# PROC051C_XDS110_Interface_1B.net
KiCad netlist of a schematic drawn in Altium Designer
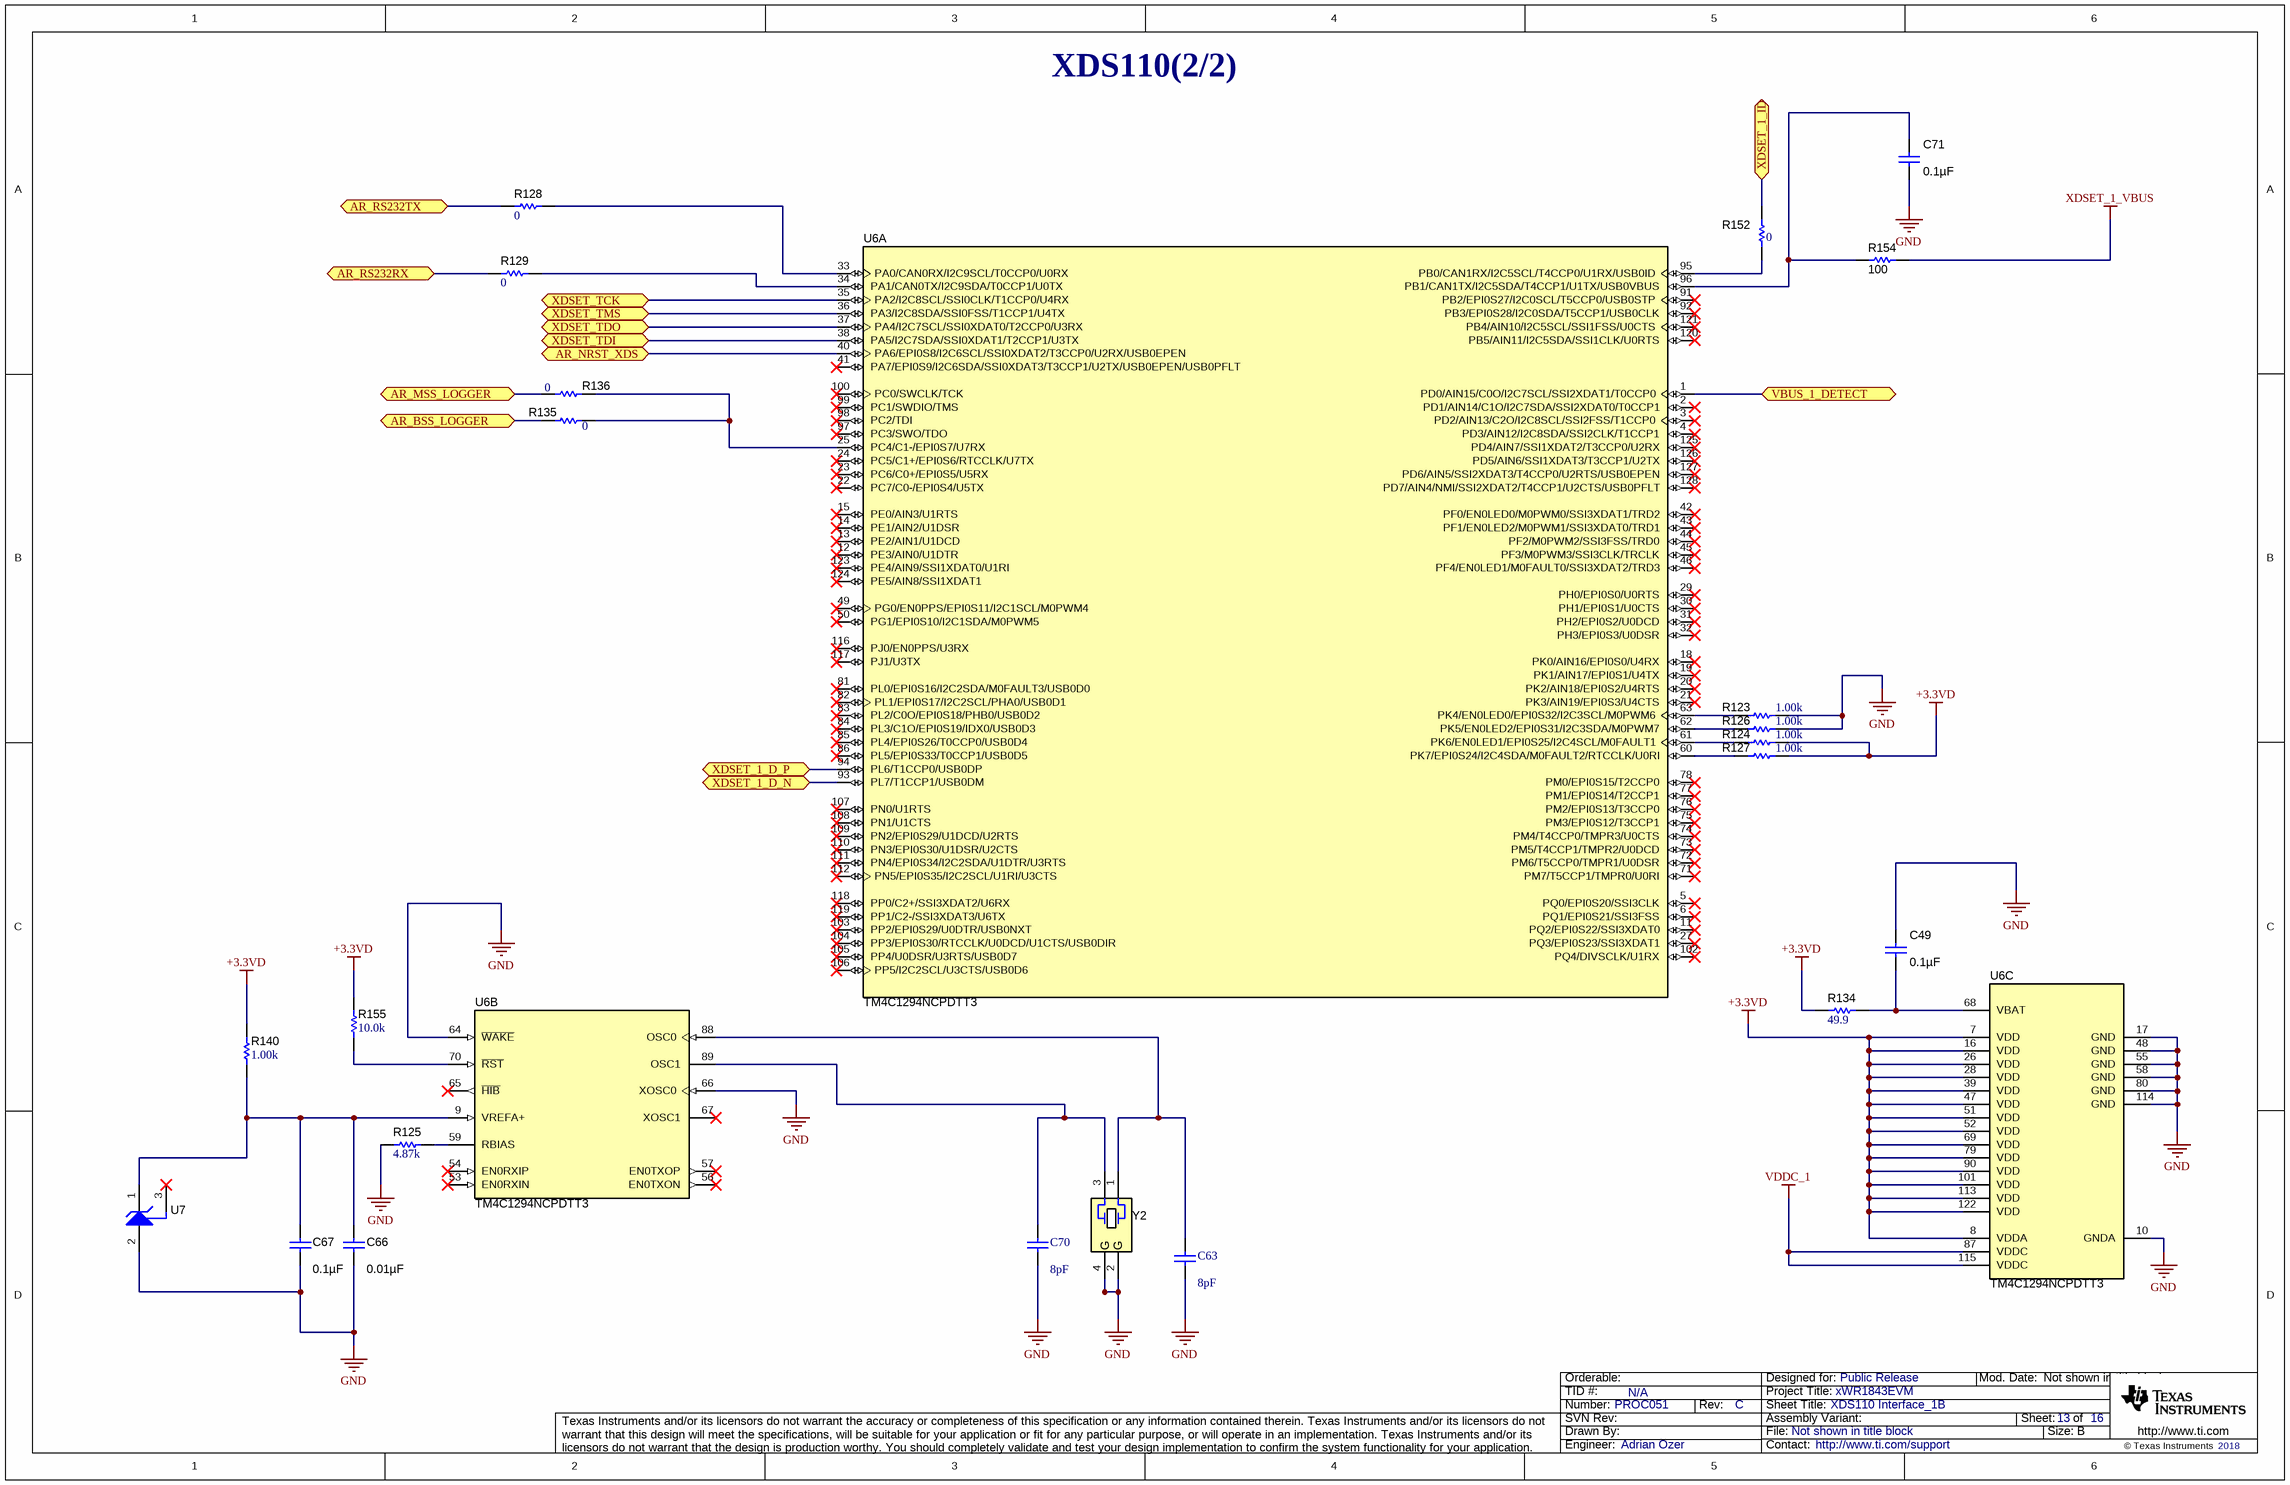
[diagram p0: PROC051C_XDS110 Interface_1B.SchDoc]

(export (version "E")
  (design (tool "Eeschema 10.0.6"))
  (components
    (comp (ref "C49")
      (value "C0402C104K8RACTU")
      (footprint "0402L")
      (description "CAP, CERM, 0.1 µF, 10 V,+/- 10%, X7R, 0402")
      (fields (field (name "MANUFACTURER") "Kemet") (field (name "VALUEDISPLAYED") "0.1µF"))
      (libsource (lib "Altium Vault - TI") (part "CMP-0078241-1"))
    )
    (comp (ref "C63")
      (value "GCM1555C1H8R0DA16D")
      (footprint "0402L")
      (description "Cap Ceramic 8pF 50V C0G 0.5pF SMD 0402 125C Paper T/R")
      (fields (field (name "CAP_F") "8pF") (field (name "MANUFACTURER") "Murata Electronics North America"))
      (libsource (lib "Altium Vault - TI") (part "CMP-0087060-3"))
    )
    (comp (ref "C66")
      (value "C0402C103K4RACTU")
      (footprint "0402L")
      (description "CAP, CERM, 0.01 µF, 16 V,+/- 10%, X7R, 0402")
      (fields (field (name "MANUFACTURER") "Kemet") (field (name "VALUEDISPLAYED") "0.01µF"))
      (libsource (lib "Altium Vault - TI") (part "Capacitor"))
    )
    (comp (ref "C67")
      (value "C0402C104K8RACTU")
      (footprint "0402L")
      (description "CAP, CERM, 0.1 µF, 10 V,+/- 10%, X7R, 0402")
      (fields (field (name "MANUFACTURER") "Kemet") (field (name "VALUEDISPLAYED") "0.1µF"))
      (libsource (lib "Altium Vault - TI") (part "Capacitor"))
    )
    (comp (ref "C70")
      (value "GCM1555C1H8R0DA16D")
      (footprint "0402L")
      (description "Cap Ceramic 8pF 50V C0G 0.5pF SMD 0402 125C Paper T/R")
      (fields (field (name "CAP_F") "8pF") (field (name "MANUFACTURER") "Murata Electronics North America"))
      (libsource (lib "Altium Vault - TI") (part "CMP-0087060-3"))
    )
    (comp (ref "C71")
      (value "C0402C104K8RACTU")
      (footprint "0402L")
      (description "CAP, CERM, 0.1 µF, 10 V,+/- 10%, X7R, 0402")
      (fields (field (name "MANUFACTURER") "Kemet") (field (name "VALUEDISPLAYED") "0.1µF"))
      (libsource (lib "Altium Vault - TI") (part "Capacitor"))
    )
    (comp (ref "R123")
      (value "CRCW04021K00FKED")
      (footprint "0402L")
      (description "RES, 1.00 k, 1%, 0.063 W, AEC-Q200 Grade 0, 0402")
      (fields (field (name "MANUFACTURER") "Vishay-Dale") (field (name "VALUEDISPLAYED") "1.00k"))
      (libsource (lib "Altium Vault - TI") (part "Resistor"))
    )
    (comp (ref "R124")
      (value "CRCW04021K00FKED")
      (footprint "0402L")
      (description "RES, 1.00 k, 1%, 0.063 W, AEC-Q200 Grade 0, 0402")
      (fields (field (name "MANUFACTURER") "Vishay-Dale") (field (name "VALUEDISPLAYED") "1.00k"))
      (libsource (lib "Altium Vault - TI") (part "Resistor"))
    )
    (comp (ref "R125")
      (value "CRCW04024K87FKED")
      (footprint "0402L")
      (description "RES, 4.87 k, 1%, 0.063 W, AEC-Q200 Grade 0, 0402")
      (fields (field (name "MANUFACTURER") "Vishay-Dale") (field (name "VALUEDISPLAYED") "4.87k"))
      (libsource (lib "Altium Vault - TI") (part "Resistor"))
    )
    (comp (ref "R126")
      (value "CRCW04021K00FKED")
      (footprint "0402L")
      (description "RES, 1.00 k, 1%, 0.063 W, AEC-Q200 Grade 0, 0402")
      (fields (field (name "MANUFACTURER") "Vishay-Dale") (field (name "VALUEDISPLAYED") "1.00k"))
      (libsource (lib "Altium Vault - TI") (part "Resistor"))
    )
    (comp (ref "R127")
      (value "CRCW04021K00FKED")
      (footprint "0402L")
      (description "RES, 1.00 k, 1%, 0.063 W, AEC-Q200 Grade 0, 0402")
      (fields (field (name "MANUFACTURER") "Vishay-Dale") (field (name "VALUEDISPLAYED") "1.00k"))
      (libsource (lib "Altium Vault - TI") (part "Resistor"))
    )
    (comp (ref "R128")
      (value "ERJ-2GE0R00X")
      (footprint "0402L")
      (description "RES, 0, 5%, 0.1 W, AEC-Q200 Grade 0, 0402")
      (fields (field (name "MANUFACTURER") "Panasonic") (field (name "VALUEDISPLAYED") "0"))
      (libsource (lib "Altium Vault - TI") (part "Resistor"))
    )
    (comp (ref "R129")
      (value "ERJ-2GE0R00X")
      (footprint "0402L")
      (description "RES, 0, 5%, 0.1 W, AEC-Q200 Grade 0, 0402")
      (fields (field (name "MANUFACTURER") "Panasonic") (field (name "VALUEDISPLAYED") "0"))
      (libsource (lib "Altium Vault - TI") (part "Resistor"))
    )
    (comp (ref "R134")
      (value "CRCW040249R9FKED")
      (footprint "0402L")
      (description "RES, 49.9, 1%, 0.063 W, AEC-Q200 Grade 0, 0402")
      (fields (field (name "MANUFACTURER") "Vishay-Dale") (field (name "VALUEDISPLAYED") "49.9"))
      (libsource (lib "Altium Vault - TI") (part "Resistor"))
    )
    (comp (ref "R135")
      (value "CRCW02010000Z0ED")
      (footprint "0201_Silk")
      (description "RES, 0, 5%, 0.05 W, 0201")
      (fields (field (name "MANUFACTURER") "Vishay-Dale") (field (name "VALUEDISPLAYED") "0"))
      (libsource (lib "Altium Vault - TI") (part "Resistor"))
    )
    (comp (ref "R136")
      (value "CRCW02010000Z0ED")
      (footprint "0201_Silk")
      (description "RES, 0, 5%, 0.05 W, 0201")
      (fields (field (name "MANUFACTURER") "Vishay-Dale") (field (name "VALUEDISPLAYED") "0"))
      (libsource (lib "Altium Vault - TI") (part "Resistor"))
    )
    (comp (ref "R140")
      (value "CRCW04021K00FKED")
      (footprint "0402L")
      (description "RES, 1.00 k, 1%, 0.063 W, AEC-Q200 Grade 0, 0402")
      (fields (field (name "MANUFACTURER") "Vishay-Dale") (field (name "VALUEDISPLAYED") "1.00k"))
      (libsource (lib "Altium Vault - TI") (part "Resistor"))
    )
    (comp (ref "R152")
      (value "ERJ-2GE0R00X")
      (footprint "0402L")
      (description "RES, 0, 5%, 0.1 W, AEC-Q200 Grade 0, 0402")
      (fields (field (name "MANUFACTURER") "Panasonic") (field (name "VALUEDISPLAYED") "0"))
      (libsource (lib "Altium Vault - TI") (part "Resistor"))
    )
    (comp (ref "R154")
      (value "ERJ-2GEJ101X")
      (footprint "0402L")
      (description "RES, 100, 5%, 0.1 W, AEC-Q200 Grade 0, 0402")
      (fields
        (field (name "MANUFACTURER") "Panasonic")
        (field (name "VALUEDISPLAYED") "100")
        (field (name "PUBLISHER") "Texas Instruments")
      )
      (libsource (lib "Altium Vault - TI") (part "Resistor"))
    )
    (comp (ref "R155")
      (value "CRCW040210K0FKED")
      (footprint "0402L")
      (description "RES, 10.0 k, 1%, 0.063 W, AEC-Q200 Grade 0, 0402")
      (fields (field (name "MANUFACTURER") "Vishay-Dale") (field (name "VALUEDISPLAYED") "10.0k"))
      (libsource (lib "Altium Vault - TI") (part "Resistor"))
    )
    (comp (ref "U6")
      (value "TM4C1294NCPDTT3")
      (footprint "PDT0128A")
      (fields (field (name "PARTNUMBER") "TM4C1294NCPDTT3") (field (name "MANUFACTURER") "Texas Instruments"))
      (libsource (lib "Altium Vault - TI") (part "TI-TM4C1294NCPDT-128"))
    )
    (comp (ref "U7")
      (value "LM4040C25QDBZR")
      (footprint "DBZ0003A_N")
      (fields (field (name "MANUFACTURER") "Texas Instruments"))
      (libsource (lib "Altium Vault - TI") (part "TI-LM4040C25DBZ3"))
    )
    (comp (ref "Y2")
      (value "NX3225SA-16.000M-STD-CRS-2")
      (footprint "NDK_NX3225SA")
      (description "Crystal, 16 MHz, 15 ppm, 8 pF, AEC-Q200 Grade 1, SMD")
      (fields (field (name "MANUFACTURER") "NDK"))
      (libsource (lib "Altium Vault - TI") (part "CMP-0078214-2"))
    )
  )
  (nets
    (net (code "1") (name "+3.3VD") (class "Default")
      (node (ref "R124") (pin "2") (pinfunction "2_2") (pintype "passive"))
      (node (ref "R127") (pin "2") (pinfunction "2_2") (pintype "passive"))
      (node (ref "R134") (pin "2") (pinfunction "2_2") (pintype "passive"))
      (node (ref "R140") (pin "2") (pinfunction "2_2") (pintype "passive"))
      (node (ref "R155") (pin "2") (pinfunction "2_2") (pintype "passive"))
      (node (ref "U6") (pin "101") (pinfunction "VDD_101") (pintype "power_in"))
      (node (ref "U6") (pin "113") (pinfunction "VDD_113") (pintype "power_in"))
      (node (ref "U6") (pin "122") (pinfunction "VDD_122") (pintype "power_in"))
      (node (ref "U6") (pin "16") (pinfunction "VDD_16") (pintype "power_in"))
      (node (ref "U6") (pin "26") (pinfunction "VDD_26") (pintype "power_in"))
      (node (ref "U6") (pin "28") (pinfunction "VDD_28") (pintype "power_in"))
      (node (ref "U6") (pin "39") (pinfunction "VDD_39") (pintype "power_in"))
      (node (ref "U6") (pin "47") (pinfunction "VDD_47") (pintype "power_in"))
      (node (ref "U6") (pin "51") (pinfunction "VDD_51") (pintype "power_in"))
      (node (ref "U6") (pin "52") (pinfunction "VDD_52") (pintype "power_in"))
      (node (ref "U6") (pin "69") (pinfunction "VDD_69") (pintype "power_in"))
      (node (ref "U6") (pin "7") (pinfunction "VDD_7") (pintype "power_in"))
      (node (ref "U6") (pin "79") (pinfunction "VDD_79") (pintype "power_in"))
      (node (ref "U6") (pin "8") (pinfunction "VDDA_8") (pintype "power_in"))
      (node (ref "U6") (pin "90") (pinfunction "VDD_90") (pintype "power_in"))
    )
    (net (code "2") (name "/AR_BSS_LOGGER") (class "Default")
      (node (ref "R135") (pin "1") (pinfunction "1_1") (pintype "passive"))
    )
    (net (code "3") (name "/AR_MSS_LOGGER") (class "Default")
      (node (ref "R136") (pin "1") (pinfunction "1_1") (pintype "passive"))
    )
    (net (code "4") (name "/AR_NRST_XDS") (class "Default")
      (node (ref "U6") (pin "40") (pinfunction "PA6/EPI0S8/I2C6SCL/SSI0XDAT2/T3CCP0/U2RX/USB0EPEN_40") (pintype "bidirectional"))
    )
    (net (code "5") (name "/AR_RS232RX") (class "Default")
      (node (ref "R129") (pin "1") (pinfunction "1_1") (pintype "passive"))
    )
    (net (code "6") (name "/AR_RS232TX") (class "Default")
      (node (ref "R128") (pin "1") (pinfunction "1_1") (pintype "passive"))
    )
    (net (code "7") (name "/VBUS_1_DETECT") (class "Default")
      (node (ref "U6") (pin "1") (pinfunction "PD0/AIN15/C0O/I2C7SCL/SSI2XDAT1/T0CCP0_1") (pintype "bidirectional"))
    )
    (net (code "8") (name "/XDSET_1_D_N") (class "Default")
      (node (ref "U6") (pin "93") (pinfunction "PL7/T1CCP1/USB0DM_93") (pintype "bidirectional"))
    )
    (net (code "9") (name "/XDSET_1_D_P") (class "Default")
      (node (ref "U6") (pin "94") (pinfunction "PL6/T1CCP0/USB0DP_94") (pintype "bidirectional"))
    )
    (net (code "10") (name "/XDSET_1_ID") (class "Default")
      (node (ref "R152") (pin "2") (pinfunction "2_2") (pintype "passive"))
    )
    (net (code "11") (name "/XDSET_TCK") (class "Default")
      (node (ref "U6") (pin "35") (pinfunction "PA2/I2C8SCL/SSI0CLK/T1CCP0/U4RX_35") (pintype "bidirectional"))
    )
    (net (code "12") (name "/XDSET_TDI") (class "Default")
      (node (ref "U6") (pin "38") (pinfunction "PA5/I2C7SDA/SSI0XDAT1/T2CCP1/U3TX_38") (pintype "bidirectional"))
    )
    (net (code "13") (name "/XDSET_TDO") (class "Default")
      (node (ref "U6") (pin "37") (pinfunction "PA4/I2C7SCL/SSI0XDAT0/T2CCP0/U3RX_37") (pintype "bidirectional"))
    )
    (net (code "14") (name "/XDSET_TMS") (class "Default")
      (node (ref "U6") (pin "36") (pinfunction "PA3/I2C8SDA/SSI0FSS/T1CCP1/U4TX_36") (pintype "bidirectional"))
    )
    (net (code "15") (name "GND") (class "Default")
      (node (ref "C49") (pin "1") (pinfunction "1_1") (pintype "passive"))
      (node (ref "C63") (pin "2") (pinfunction "2_2") (pintype "passive"))
      (node (ref "C66") (pin "1") (pinfunction "1_1") (pintype "passive"))
      (node (ref "C67") (pin "1") (pinfunction "1_1") (pintype "passive"))
      (node (ref "C70") (pin "2") (pinfunction "2_2") (pintype "passive"))
      (node (ref "C71") (pin "1") (pinfunction "1_1") (pintype "passive"))
      (node (ref "R123") (pin "2") (pinfunction "2_2") (pintype "passive"))
      (node (ref "R125") (pin "1") (pinfunction "1_1") (pintype "passive"))
      (node (ref "R126") (pin "2") (pinfunction "2_2") (pintype "passive"))
      (node (ref "U6") (pin "10") (pinfunction "GNDA_10") (pintype "power_in"))
      (node (ref "U6") (pin "114") (pinfunction "GND_114") (pintype "power_in"))
      (node (ref "U6") (pin "17") (pinfunction "GND_17") (pintype "power_in"))
      (node (ref "U6") (pin "48") (pinfunction "GND_48") (pintype "power_in"))
      (node (ref "U6") (pin "55") (pinfunction "GND_55") (pintype "power_in"))
      (node (ref "U6") (pin "58") (pinfunction "GND_58") (pintype "power_in"))
      (node (ref "U6") (pin "64") (pinfunction "~{WAKE}_64") (pintype "input"))
      (node (ref "U6") (pin "66") (pinfunction "XOSC0_66") (pintype "input"))
      (node (ref "U6") (pin "80") (pinfunction "GND_80") (pintype "power_in"))
      (node (ref "U7") (pin "2") (pinfunction "ANODE_2") (pintype "passive"))
      (node (ref "Y2") (pin "2") (pinfunction "GND_2") (pintype "power_in"))
      (node (ref "Y2") (pin "4") (pinfunction "GND_4") (pintype "power_in"))
    )
    (net (code "16") (name "Net-(U6A-PA0{slash}CAN0RX{slash}I2C9SCL{slash}T0CCP0{slash}U0RX)") (class "Default")
      (node (ref "R128") (pin "2") (pinfunction "2_2") (pintype "passive"))
      (node (ref "U6") (pin "33") (pinfunction "PA0/CAN0RX/I2C9SCL/T0CCP0/U0RX_33") (pintype "bidirectional"))
    )
    (net (code "17") (name "Net-(U6A-PA1{slash}CAN0TX{slash}I2C9SDA{slash}T0CCP1{slash}U0TX)") (class "Default")
      (node (ref "R129") (pin "2") (pinfunction "2_2") (pintype "passive"))
      (node (ref "U6") (pin "34") (pinfunction "PA1/CAN0TX/I2C9SDA/T0CCP1/U0TX_34") (pintype "bidirectional"))
    )
    (net (code "18") (name "Net-(U6A-PB0{slash}CAN1RX{slash}I2C5SCL{slash}T4CCP0{slash}U1RX{slash}USB0ID)") (class "Default")
      (node (ref "R152") (pin "1") (pinfunction "1_1") (pintype "passive"))
      (node (ref "U6") (pin "95") (pinfunction "PB0/CAN1RX/I2C5SCL/T4CCP0/U1RX/USB0ID_95") (pintype "bidirectional"))
    )
    (net (code "19") (name "Net-(U6A-PB1{slash}CAN1TX{slash}I2C5SDA{slash}T4CCP1{slash}U1TX{slash}USB0VBUS)") (class "Default")
      (node (ref "C71") (pin "2") (pinfunction "2_2") (pintype "passive"))
      (node (ref "R154") (pin "1") (pinfunction "1_1") (pintype "passive"))
      (node (ref "U6") (pin "96") (pinfunction "PB1/CAN1TX/I2C5SDA/T4CCP1/U1TX/USB0VBUS_96") (pintype "bidirectional"))
    )
    (net (code "20") (name "Net-(U6A-PC4{slash}C1-{slash}EPI0S7{slash}U7RX)") (class "Default")
      (node (ref "R135") (pin "2") (pinfunction "2_2") (pintype "passive"))
      (node (ref "R136") (pin "2") (pinfunction "2_2") (pintype "passive"))
      (node (ref "U6") (pin "25") (pinfunction "PC4/C1-/EPI0S7/U7RX_25") (pintype "bidirectional"))
    )
    (net (code "21") (name "Net-(U6A-PK4{slash}EN0LED0{slash}EPI0S32{slash}I2C3SCL{slash}M0PWM6)") (class "Default")
      (node (ref "R123") (pin "1") (pinfunction "1_1") (pintype "passive"))
      (node (ref "U6") (pin "63") (pinfunction "PK4/EN0LED0/EPI0S32/I2C3SCL/M0PWM6_63") (pintype "bidirectional"))
    )
    (net (code "22") (name "Net-(U6A-PK5{slash}EN0LED2{slash}EPI0S31{slash}I2C3SDA{slash}M0PWM7)") (class "Default")
      (node (ref "R126") (pin "1") (pinfunction "1_1") (pintype "passive"))
      (node (ref "U6") (pin "62") (pinfunction "PK5/EN0LED2/EPI0S31/I2C3SDA/M0PWM7_62") (pintype "bidirectional"))
    )
    (net (code "23") (name "Net-(U6A-PK6{slash}EN0LED1{slash}EPI0S25{slash}I2C4SCL{slash}M0FAULT1)") (class "Default")
      (node (ref "R124") (pin "1") (pinfunction "1_1") (pintype "passive"))
      (node (ref "U6") (pin "61") (pinfunction "PK6/EN0LED1/EPI0S25/I2C4SCL/M0FAULT1_61") (pintype "bidirectional"))
    )
    (net (code "24") (name "Net-(U6A-PK7{slash}EPI0S24{slash}I2C4SDA{slash}M0FAULT2{slash}RTCCLK{slash}U0RI)") (class "Default")
      (node (ref "R127") (pin "1") (pinfunction "1_1") (pintype "passive"))
      (node (ref "U6") (pin "60") (pinfunction "PK7/EPI0S24/I2C4SDA/M0FAULT2/RTCCLK/U0RI_60") (pintype "bidirectional"))
    )
    (net (code "25") (name "Net-(U6B-OSC0)") (class "Default")
      (node (ref "C63") (pin "1") (pinfunction "1_1") (pintype "passive"))
      (node (ref "U6") (pin "88") (pinfunction "OSC0_88") (pintype "input"))
      (node (ref "Y2") (pin "1") (pinfunction "1_1") (pintype "passive"))
    )
    (net (code "26") (name "Net-(U6B-OSC1)") (class "Default")
      (node (ref "C70") (pin "1") (pinfunction "1_1") (pintype "passive"))
      (node (ref "U6") (pin "89") (pinfunction "OSC1_89") (pintype "passive"))
      (node (ref "Y2") (pin "3") (pinfunction "3_3") (pintype "passive"))
    )
    (net (code "27") (name "Net-(U6B-RBIAS)") (class "Default")
      (node (ref "R125") (pin "2") (pinfunction "2_2") (pintype "passive"))
      (node (ref "U6") (pin "59") (pinfunction "RBIAS_59") (pintype "passive"))
    )
    (net (code "28") (name "Net-(U6B-VREFA+)") (class "Default")
      (node (ref "C66") (pin "2") (pinfunction "2_2") (pintype "passive"))
      (node (ref "C67") (pin "2") (pinfunction "2_2") (pintype "passive"))
      (node (ref "R140") (pin "1") (pinfunction "1_1") (pintype "passive"))
      (node (ref "U6") (pin "9") (pinfunction "VREFA+_9") (pintype "input"))
      (node (ref "U7") (pin "1") (pinfunction "CATHODE_1") (pintype "passive"))
    )
    (net (code "29") (name "Net-(U6B-~{RST})") (class "Default")
      (node (ref "R155") (pin "1") (pinfunction "1_1") (pintype "passive"))
      (node (ref "U6") (pin "70") (pinfunction "~{RST}_70") (pintype "input"))
    )
    (net (code "30") (name "Net-(U6C-VBAT)") (class "Default")
      (node (ref "C49") (pin "2") (pinfunction "2_2") (pintype "passive"))
      (node (ref "R134") (pin "1") (pinfunction "1_1") (pintype "passive"))
      (node (ref "U6") (pin "68") (pinfunction "VBAT_68") (pintype "power_in"))
    )
    (net (code "31") (name "VDDC_1") (class "Default")
      (node (ref "U6") (pin "115") (pinfunction "VDDC_115") (pintype "power_in"))
      (node (ref "U6") (pin "87") (pinfunction "VDDC_87") (pintype "power_in"))
    )
    (net (code "32") (name "XDSET_1_VBUS") (class "Default")
      (node (ref "R154") (pin "2") (pinfunction "2_2") (pintype "passive"))
    )
    (net (code "33") (name "unconnected-(U6A-PA7{slash}EPI0S9{slash}I2C6SDA{slash}SSI0XDAT3{slash}T3CCP1{slash}U2TX{slash}USB0EPEN{slash}USB0PFLT-Pad41)") (class "Default")
      (node (ref "U6") (pin "41") (pinfunction "PA7/EPI0S9/I2C6SDA/SSI0XDAT3/T3CCP1/U2TX/USB0EPEN/USB0PFLT_41") (pintype "bidirectional+no_connect"))
    )
    (net (code "34") (name "unconnected-(U6A-PB2{slash}EPI0S27{slash}I2C0SCL{slash}T5CCP0{slash}USB0STP-Pad91)") (class "Default")
      (node (ref "U6") (pin "91") (pinfunction "PB2/EPI0S27/I2C0SCL/T5CCP0/USB0STP_91") (pintype "bidirectional+no_connect"))
    )
    (net (code "35") (name "unconnected-(U6A-PB3{slash}EPI0S28{slash}I2C0SDA{slash}T5CCP1{slash}USB0CLK-Pad92)") (class "Default")
      (node (ref "U6") (pin "92") (pinfunction "PB3/EPI0S28/I2C0SDA/T5CCP1/USB0CLK_92") (pintype "bidirectional+no_connect"))
    )
    (net (code "36") (name "unconnected-(U6A-PB4{slash}AIN10{slash}I2C5SCL{slash}SSI1FSS{slash}U0CTS-Pad121)") (class "Default")
      (node (ref "U6") (pin "121") (pinfunction "PB4/AIN10/I2C5SCL/SSI1FSS/U0CTS_121") (pintype "bidirectional+no_connect"))
    )
    (net (code "37") (name "unconnected-(U6A-PB5{slash}AIN11{slash}I2C5SDA{slash}SSI1CLK{slash}U0RTS-Pad120)") (class "Default")
      (node (ref "U6") (pin "120") (pinfunction "PB5/AIN11/I2C5SDA/SSI1CLK/U0RTS_120") (pintype "bidirectional+no_connect"))
    )
    (net (code "38") (name "unconnected-(U6A-PC0{slash}SWCLK{slash}TCK-Pad100)") (class "Default")
      (node (ref "U6") (pin "100") (pinfunction "PC0/SWCLK/TCK_100") (pintype "bidirectional+no_connect"))
    )
    (net (code "39") (name "unconnected-(U6A-PC1{slash}SWDIO{slash}TMS-Pad99)") (class "Default")
      (node (ref "U6") (pin "99") (pinfunction "PC1/SWDIO/TMS_99") (pintype "bidirectional+no_connect"))
    )
    (net (code "40") (name "unconnected-(U6A-PC2{slash}TDI-Pad98)") (class "Default")
      (node (ref "U6") (pin "98") (pinfunction "PC2/TDI_98") (pintype "bidirectional+no_connect"))
    )
    (net (code "41") (name "unconnected-(U6A-PC3{slash}SWO{slash}TDO-Pad97)") (class "Default")
      (node (ref "U6") (pin "97") (pinfunction "PC3/SWO/TDO_97") (pintype "bidirectional+no_connect"))
    )
    (net (code "42") (name "unconnected-(U6A-PC5{slash}C1+{slash}EPI0S6{slash}RTCCLK{slash}U7TX-Pad24)") (class "Default")
      (node (ref "U6") (pin "24") (pinfunction "PC5/C1+/EPI0S6/RTCCLK/U7TX_24") (pintype "bidirectional+no_connect"))
    )
    (net (code "43") (name "unconnected-(U6A-PC6{slash}C0+{slash}EPI0S5{slash}U5RX-Pad23)") (class "Default")
      (node (ref "U6") (pin "23") (pinfunction "PC6/C0+/EPI0S5/U5RX_23") (pintype "bidirectional+no_connect"))
    )
    (net (code "44") (name "unconnected-(U6A-PC7{slash}C0-{slash}EPI0S4{slash}U5TX-Pad22)") (class "Default")
      (node (ref "U6") (pin "22") (pinfunction "PC7/C0-/EPI0S4/U5TX_22") (pintype "bidirectional+no_connect"))
    )
    (net (code "45") (name "unconnected-(U6A-PD1{slash}AIN14{slash}C1O{slash}I2C7SDA{slash}SSI2XDAT0{slash}T0CCP1-Pad2)") (class "Default")
      (node (ref "U6") (pin "2") (pinfunction "PD1/AIN14/C1O/I2C7SDA/SSI2XDAT0/T0CCP1_2") (pintype "bidirectional+no_connect"))
    )
    (net (code "46") (name "unconnected-(U6A-PD2{slash}AIN13{slash}C2O{slash}I2C8SCL{slash}SSI2FSS{slash}T1CCP0-Pad3)") (class "Default")
      (node (ref "U6") (pin "3") (pinfunction "PD2/AIN13/C2O/I2C8SCL/SSI2FSS/T1CCP0_3") (pintype "bidirectional+no_connect"))
    )
    (net (code "47") (name "unconnected-(U6A-PD3{slash}AIN12{slash}I2C8SDA{slash}SSI2CLK{slash}T1CCP1-Pad4)") (class "Default")
      (node (ref "U6") (pin "4") (pinfunction "PD3/AIN12/I2C8SDA/SSI2CLK/T1CCP1_4") (pintype "bidirectional+no_connect"))
    )
    (net (code "48") (name "unconnected-(U6A-PD4{slash}AIN7{slash}SSI1XDAT2{slash}T3CCP0{slash}U2RX-Pad125)") (class "Default")
      (node (ref "U6") (pin "125") (pinfunction "PD4/AIN7/SSI1XDAT2/T3CCP0/U2RX_125") (pintype "bidirectional+no_connect"))
    )
    (net (code "49") (name "unconnected-(U6A-PD5{slash}AIN6{slash}SSI1XDAT3{slash}T3CCP1{slash}U2TX-Pad126)") (class "Default")
      (node (ref "U6") (pin "126") (pinfunction "PD5/AIN6/SSI1XDAT3/T3CCP1/U2TX_126") (pintype "bidirectional+no_connect"))
    )
    (net (code "50") (name "unconnected-(U6A-PD6{slash}AIN5{slash}SSI2XDAT3{slash}T4CCP0{slash}U2RTS{slash}USB0EPEN-Pad127)") (class "Default")
      (node (ref "U6") (pin "127") (pinfunction "PD6/AIN5/SSI2XDAT3/T4CCP0/U2RTS/USB0EPEN_127") (pintype "bidirectional+no_connect"))
    )
    (net (code "51") (name "unconnected-(U6A-PD7{slash}AIN4{slash}NMI{slash}SSI2XDAT2{slash}T4CCP1{slash}U2CTS{slash}USB0PFLT-Pad128)") (class "Default")
      (node (ref "U6") (pin "128") (pinfunction "PD7/AIN4/NMI/SSI2XDAT2/T4CCP1/U2CTS/USB0PFLT_128") (pintype "bidirectional+no_connect"))
    )
    (net (code "52") (name "unconnected-(U6A-PE0{slash}AIN3{slash}U1RTS-Pad15)") (class "Default")
      (node (ref "U6") (pin "15") (pinfunction "PE0/AIN3/U1RTS_15") (pintype "bidirectional+no_connect"))
    )
    (net (code "53") (name "unconnected-(U6A-PE1{slash}AIN2{slash}U1DSR-Pad14)") (class "Default")
      (node (ref "U6") (pin "14") (pinfunction "PE1/AIN2/U1DSR_14") (pintype "bidirectional+no_connect"))
    )
    (net (code "54") (name "unconnected-(U6A-PE2{slash}AIN1{slash}U1DCD-Pad13)") (class "Default")
      (node (ref "U6") (pin "13") (pinfunction "PE2/AIN1/U1DCD_13") (pintype "bidirectional+no_connect"))
    )
    (net (code "55") (name "unconnected-(U6A-PE3{slash}AIN0{slash}U1DTR-Pad12)") (class "Default")
      (node (ref "U6") (pin "12") (pinfunction "PE3/AIN0/U1DTR_12") (pintype "bidirectional+no_connect"))
    )
    (net (code "56") (name "unconnected-(U6A-PE4{slash}AIN9{slash}SSI1XDAT0{slash}U1RI-Pad123)") (class "Default")
      (node (ref "U6") (pin "123") (pinfunction "PE4/AIN9/SSI1XDAT0/U1RI_123") (pintype "bidirectional+no_connect"))
    )
    (net (code "57") (name "unconnected-(U6A-PE5{slash}AIN8{slash}SSI1XDAT1-Pad124)") (class "Default")
      (node (ref "U6") (pin "124") (pinfunction "PE5/AIN8/SSI1XDAT1_124") (pintype "bidirectional+no_connect"))
    )
    (net (code "58") (name "unconnected-(U6A-PF0{slash}EN0LED0{slash}M0PWM0{slash}SSI3XDAT1{slash}TRD2-Pad42)") (class "Default")
      (node (ref "U6") (pin "42") (pinfunction "PF0/EN0LED0/M0PWM0/SSI3XDAT1/TRD2_42") (pintype "bidirectional+no_connect"))
    )
    (net (code "59") (name "unconnected-(U6A-PF1{slash}EN0LED2{slash}M0PWM1{slash}SSI3XDAT0{slash}TRD1-Pad43)") (class "Default")
      (node (ref "U6") (pin "43") (pinfunction "PF1/EN0LED2/M0PWM1/SSI3XDAT0/TRD1_43") (pintype "bidirectional+no_connect"))
    )
    (net (code "60") (name "unconnected-(U6A-PF2{slash}M0PWM2{slash}SSI3FSS{slash}TRD0-Pad44)") (class "Default")
      (node (ref "U6") (pin "44") (pinfunction "PF2/M0PWM2/SSI3FSS/TRD0_44") (pintype "bidirectional+no_connect"))
    )
    (net (code "61") (name "unconnected-(U6A-PF3{slash}M0PWM3{slash}SSI3CLK{slash}TRCLK-Pad45)") (class "Default")
      (node (ref "U6") (pin "45") (pinfunction "PF3/M0PWM3/SSI3CLK/TRCLK_45") (pintype "bidirectional+no_connect"))
    )
    (net (code "62") (name "unconnected-(U6A-PF4{slash}EN0LED1{slash}M0FAULT0{slash}SSI3XDAT2{slash}TRD3-Pad46)") (class "Default")
      (node (ref "U6") (pin "46") (pinfunction "PF4/EN0LED1/M0FAULT0/SSI3XDAT2/TRD3_46") (pintype "bidirectional+no_connect"))
    )
    (net (code "63") (name "unconnected-(U6A-PG0{slash}EN0PPS{slash}EPI0S11{slash}I2C1SCL{slash}M0PWM4-Pad49)") (class "Default")
      (node (ref "U6") (pin "49") (pinfunction "PG0/EN0PPS/EPI0S11/I2C1SCL/M0PWM4_49") (pintype "bidirectional+no_connect"))
    )
    (net (code "64") (name "unconnected-(U6A-PG1{slash}EPI0S10{slash}I2C1SDA{slash}M0PWM5-Pad50)") (class "Default")
      (node (ref "U6") (pin "50") (pinfunction "PG1/EPI0S10/I2C1SDA/M0PWM5_50") (pintype "bidirectional+no_connect"))
    )
    (net (code "65") (name "unconnected-(U6A-PH0{slash}EPI0S0{slash}U0RTS-Pad29)") (class "Default")
      (node (ref "U6") (pin "29") (pinfunction "PH0/EPI0S0/U0RTS_29") (pintype "bidirectional+no_connect"))
    )
    (net (code "66") (name "unconnected-(U6A-PH1{slash}EPI0S1{slash}U0CTS-Pad30)") (class "Default")
      (node (ref "U6") (pin "30") (pinfunction "PH1/EPI0S1/U0CTS_30") (pintype "bidirectional+no_connect"))
    )
    (net (code "67") (name "unconnected-(U6A-PH2{slash}EPI0S2{slash}U0DCD-Pad31)") (class "Default")
      (node (ref "U6") (pin "31") (pinfunction "PH2/EPI0S2/U0DCD_31") (pintype "bidirectional+no_connect"))
    )
    (net (code "68") (name "unconnected-(U6A-PH3{slash}EPI0S3{slash}U0DSR-Pad32)") (class "Default")
      (node (ref "U6") (pin "32") (pinfunction "PH3/EPI0S3/U0DSR_32") (pintype "bidirectional+no_connect"))
    )
    (net (code "69") (name "unconnected-(U6A-PJ0{slash}EN0PPS{slash}U3RX-Pad116)") (class "Default")
      (node (ref "U6") (pin "116") (pinfunction "PJ0/EN0PPS/U3RX_116") (pintype "bidirectional+no_connect"))
    )
    (net (code "70") (name "unconnected-(U6A-PJ1{slash}U3TX-Pad117)") (class "Default")
      (node (ref "U6") (pin "117") (pinfunction "PJ1/U3TX_117") (pintype "bidirectional+no_connect"))
    )
    (net (code "71") (name "unconnected-(U6A-PK0{slash}AIN16{slash}EPI0S0{slash}U4RX-Pad18)") (class "Default")
      (node (ref "U6") (pin "18") (pinfunction "PK0/AIN16/EPI0S0/U4RX_18") (pintype "bidirectional+no_connect"))
    )
    (net (code "72") (name "unconnected-(U6A-PK1{slash}AIN17{slash}EPI0S1{slash}U4TX-Pad19)") (class "Default")
      (node (ref "U6") (pin "19") (pinfunction "PK1/AIN17/EPI0S1/U4TX_19") (pintype "bidirectional+no_connect"))
    )
    (net (code "73") (name "unconnected-(U6A-PK2{slash}AIN18{slash}EPI0S2{slash}U4RTS-Pad20)") (class "Default")
      (node (ref "U6") (pin "20") (pinfunction "PK2/AIN18/EPI0S2/U4RTS_20") (pintype "bidirectional+no_connect"))
    )
    (net (code "74") (name "unconnected-(U6A-PK3{slash}AIN19{slash}EPI0S3{slash}U4CTS-Pad21)") (class "Default")
      (node (ref "U6") (pin "21") (pinfunction "PK3/AIN19/EPI0S3/U4CTS_21") (pintype "bidirectional+no_connect"))
    )
    (net (code "75") (name "unconnected-(U6A-PL0{slash}EPI0S16{slash}I2C2SDA{slash}M0FAULT3{slash}USB0D0-Pad81)") (class "Default")
      (node (ref "U6") (pin "81") (pinfunction "PL0/EPI0S16/I2C2SDA/M0FAULT3/USB0D0_81") (pintype "bidirectional+no_connect"))
    )
    (net (code "76") (name "unconnected-(U6A-PL1{slash}EPI0S17{slash}I2C2SCL{slash}PHA0{slash}USB0D1-Pad82)") (class "Default")
      (node (ref "U6") (pin "82") (pinfunction "PL1/EPI0S17/I2C2SCL/PHA0/USB0D1_82") (pintype "bidirectional+no_connect"))
    )
    (net (code "77") (name "unconnected-(U6A-PL2{slash}C0O{slash}EPI0S18{slash}PHB0{slash}USB0D2-Pad83)") (class "Default")
      (node (ref "U6") (pin "83") (pinfunction "PL2/C0O/EPI0S18/PHB0/USB0D2_83") (pintype "bidirectional+no_connect"))
    )
    (net (code "78") (name "unconnected-(U6A-PL3{slash}C1O{slash}EPI0S19{slash}IDX0{slash}USB0D3-Pad84)") (class "Default")
      (node (ref "U6") (pin "84") (pinfunction "PL3/C1O/EPI0S19/IDX0/USB0D3_84") (pintype "bidirectional+no_connect"))
    )
    (net (code "79") (name "unconnected-(U6A-PL4{slash}EPI0S26{slash}T0CCP0{slash}USB0D4-Pad85)") (class "Default")
      (node (ref "U6") (pin "85") (pinfunction "PL4/EPI0S26/T0CCP0/USB0D4_85") (pintype "bidirectional+no_connect"))
    )
    (net (code "80") (name "unconnected-(U6A-PL5{slash}EPI0S33{slash}T0CCP1{slash}USB0D5-Pad86)") (class "Default")
      (node (ref "U6") (pin "86") (pinfunction "PL5/EPI0S33/T0CCP1/USB0D5_86") (pintype "bidirectional+no_connect"))
    )
    (net (code "81") (name "unconnected-(U6A-PM0{slash}EPI0S15{slash}T2CCP0-Pad78)") (class "Default")
      (node (ref "U6") (pin "78") (pinfunction "PM0/EPI0S15/T2CCP0_78") (pintype "bidirectional+no_connect"))
    )
    (net (code "82") (name "unconnected-(U6A-PM1{slash}EPI0S14{slash}T2CCP1-Pad77)") (class "Default")
      (node (ref "U6") (pin "77") (pinfunction "PM1/EPI0S14/T2CCP1_77") (pintype "bidirectional+no_connect"))
    )
    (net (code "83") (name "unconnected-(U6A-PM2{slash}EPI0S13{slash}T3CCP0-Pad76)") (class "Default")
      (node (ref "U6") (pin "76") (pinfunction "PM2/EPI0S13/T3CCP0_76") (pintype "bidirectional+no_connect"))
    )
    (net (code "84") (name "unconnected-(U6A-PM3{slash}EPI0S12{slash}T3CCP1-Pad75)") (class "Default")
      (node (ref "U6") (pin "75") (pinfunction "PM3/EPI0S12/T3CCP1_75") (pintype "bidirectional+no_connect"))
    )
    (net (code "85") (name "unconnected-(U6A-PM4{slash}T4CCP0{slash}TMPR3{slash}U0CTS-Pad74)") (class "Default")
      (node (ref "U6") (pin "74") (pinfunction "PM4/T4CCP0/TMPR3/U0CTS_74") (pintype "bidirectional+no_connect"))
    )
    (net (code "86") (name "unconnected-(U6A-PM5{slash}T4CCP1{slash}TMPR2{slash}U0DCD-Pad73)") (class "Default")
      (node (ref "U6") (pin "73") (pinfunction "PM5/T4CCP1/TMPR2/U0DCD_73") (pintype "bidirectional+no_connect"))
    )
    (net (code "87") (name "unconnected-(U6A-PM6{slash}T5CCP0{slash}TMPR1{slash}U0DSR-Pad72)") (class "Default")
      (node (ref "U6") (pin "72") (pinfunction "PM6/T5CCP0/TMPR1/U0DSR_72") (pintype "bidirectional+no_connect"))
    )
    (net (code "88") (name "unconnected-(U6A-PM7{slash}T5CCP1{slash}TMPR0{slash}U0RI-Pad71)") (class "Default")
      (node (ref "U6") (pin "71") (pinfunction "PM7/T5CCP1/TMPR0/U0RI_71") (pintype "bidirectional+no_connect"))
    )
    (net (code "89") (name "unconnected-(U6A-PN0{slash}U1RTS-Pad107)") (class "Default")
      (node (ref "U6") (pin "107") (pinfunction "PN0/U1RTS_107") (pintype "bidirectional+no_connect"))
    )
    (net (code "90") (name "unconnected-(U6A-PN1{slash}U1CTS-Pad108)") (class "Default")
      (node (ref "U6") (pin "108") (pinfunction "PN1/U1CTS_108") (pintype "bidirectional+no_connect"))
    )
    (net (code "91") (name "unconnected-(U6A-PN2{slash}EPI0S29{slash}U1DCD{slash}U2RTS-Pad109)") (class "Default")
      (node (ref "U6") (pin "109") (pinfunction "PN2/EPI0S29/U1DCD/U2RTS_109") (pintype "bidirectional+no_connect"))
    )
    (net (code "92") (name "unconnected-(U6A-PN3{slash}EPI0S30{slash}U1DSR{slash}U2CTS-Pad110)") (class "Default")
      (node (ref "U6") (pin "110") (pinfunction "PN3/EPI0S30/U1DSR/U2CTS_110") (pintype "bidirectional+no_connect"))
    )
    (net (code "93") (name "unconnected-(U6A-PN4{slash}EPI0S34{slash}I2C2SDA{slash}U1DTR{slash}U3RTS-Pad111)") (class "Default")
      (node (ref "U6") (pin "111") (pinfunction "PN4/EPI0S34/I2C2SDA/U1DTR/U3RTS_111") (pintype "bidirectional+no_connect"))
    )
    (net (code "94") (name "unconnected-(U6A-PN5{slash}EPI0S35{slash}I2C2SCL{slash}U1RI{slash}U3CTS-Pad112)") (class "Default")
      (node (ref "U6") (pin "112") (pinfunction "PN5/EPI0S35/I2C2SCL/U1RI/U3CTS_112") (pintype "bidirectional+no_connect"))
    )
    (net (code "95") (name "unconnected-(U6A-PP0{slash}C2+{slash}SSI3XDAT2{slash}U6RX-Pad118)") (class "Default")
      (node (ref "U6") (pin "118") (pinfunction "PP0/C2+/SSI3XDAT2/U6RX_118") (pintype "bidirectional+no_connect"))
    )
    (net (code "96") (name "unconnected-(U6A-PP1{slash}C2-{slash}SSI3XDAT3{slash}U6TX-Pad119)") (class "Default")
      (node (ref "U6") (pin "119") (pinfunction "PP1/C2-/SSI3XDAT3/U6TX_119") (pintype "bidirectional+no_connect"))
    )
    (net (code "97") (name "unconnected-(U6A-PP2{slash}EPI0S29{slash}U0DTR{slash}USB0NXT-Pad103)") (class "Default")
      (node (ref "U6") (pin "103") (pinfunction "PP2/EPI0S29/U0DTR/USB0NXT_103") (pintype "bidirectional+no_connect"))
    )
    (net (code "98") (name "unconnected-(U6A-PP3{slash}EPI0S30{slash}RTCCLK{slash}U0DCD{slash}U1CTS{slash}USB0DIR-Pad104)") (class "Default")
      (node (ref "U6") (pin "104") (pinfunction "PP3/EPI0S30/RTCCLK/U0DCD/U1CTS/USB0DIR_104") (pintype "bidirectional+no_connect"))
    )
    (net (code "99") (name "unconnected-(U6A-PP4{slash}U0DSR{slash}U3RTS{slash}USB0D7-Pad105)") (class "Default")
      (node (ref "U6") (pin "105") (pinfunction "PP4/U0DSR/U3RTS/USB0D7_105") (pintype "bidirectional+no_connect"))
    )
    (net (code "100") (name "unconnected-(U6A-PP5{slash}I2C2SCL{slash}U3CTS{slash}USB0D6-Pad106)") (class "Default")
      (node (ref "U6") (pin "106") (pinfunction "PP5/I2C2SCL/U3CTS/USB0D6_106") (pintype "bidirectional+no_connect"))
    )
    (net (code "101") (name "unconnected-(U6A-PQ0{slash}EPI0S20{slash}SSI3CLK-Pad5)") (class "Default")
      (node (ref "U6") (pin "5") (pinfunction "PQ0/EPI0S20/SSI3CLK_5") (pintype "bidirectional+no_connect"))
    )
    (net (code "102") (name "unconnected-(U6A-PQ1{slash}EPI0S21{slash}SSI3FSS-Pad6)") (class "Default")
      (node (ref "U6") (pin "6") (pinfunction "PQ1/EPI0S21/SSI3FSS_6") (pintype "bidirectional+no_connect"))
    )
    (net (code "103") (name "unconnected-(U6A-PQ2{slash}EPI0S22{slash}SSI3XDAT0-Pad11)") (class "Default")
      (node (ref "U6") (pin "11") (pinfunction "PQ2/EPI0S22/SSI3XDAT0_11") (pintype "bidirectional+no_connect"))
    )
    (net (code "104") (name "unconnected-(U6A-PQ3{slash}EPI0S23{slash}SSI3XDAT1-Pad27)") (class "Default")
      (node (ref "U6") (pin "27") (pinfunction "PQ3/EPI0S23/SSI3XDAT1_27") (pintype "bidirectional+no_connect"))
    )
    (net (code "105") (name "unconnected-(U6A-PQ4{slash}DIVSCLK{slash}U1RX-Pad102)") (class "Default")
      (node (ref "U6") (pin "102") (pinfunction "PQ4/DIVSCLK/U1RX_102") (pintype "bidirectional+no_connect"))
    )
    (net (code "106") (name "unconnected-(U6B-EN0RXIN-Pad53)") (class "Default")
      (node (ref "U6") (pin "53") (pinfunction "EN0RXIN_53") (pintype "input+no_connect"))
    )
    (net (code "107") (name "unconnected-(U6B-EN0RXIP-Pad54)") (class "Default")
      (node (ref "U6") (pin "54") (pinfunction "EN0RXIP_54") (pintype "input+no_connect"))
    )
    (net (code "108") (name "unconnected-(U6B-EN0TXON-Pad56)") (class "Default")
      (node (ref "U6") (pin "56") (pinfunction "EN0TXON_56") (pintype "output+no_connect"))
    )
    (net (code "109") (name "unconnected-(U6B-EN0TXOP-Pad57)") (class "Default")
      (node (ref "U6") (pin "57") (pinfunction "EN0TXOP_57") (pintype "output+no_connect"))
    )
    (net (code "110") (name "unconnected-(U6B-XOSC1-Pad67)") (class "Default")
      (node (ref "U6") (pin "67") (pinfunction "XOSC1_67") (pintype "passive+no_connect"))
    )
    (net (code "111") (name "unconnected-(U6B-~{HIB}-Pad65)") (class "Default")
      (node (ref "U6") (pin "65") (pinfunction "~{HIB}_65") (pintype "output+no_connect"))
    )
    (net (code "112") (name "unconnected-(U7-NC-Pad3)") (class "Default")
      (node (ref "U7") (pin "3") (pinfunction "NC_3") (pintype "passive+no_connect"))
    )
  )
)
